# 230721-.net
KiCad netlist of a schematic drawn in EasyEDA Pro
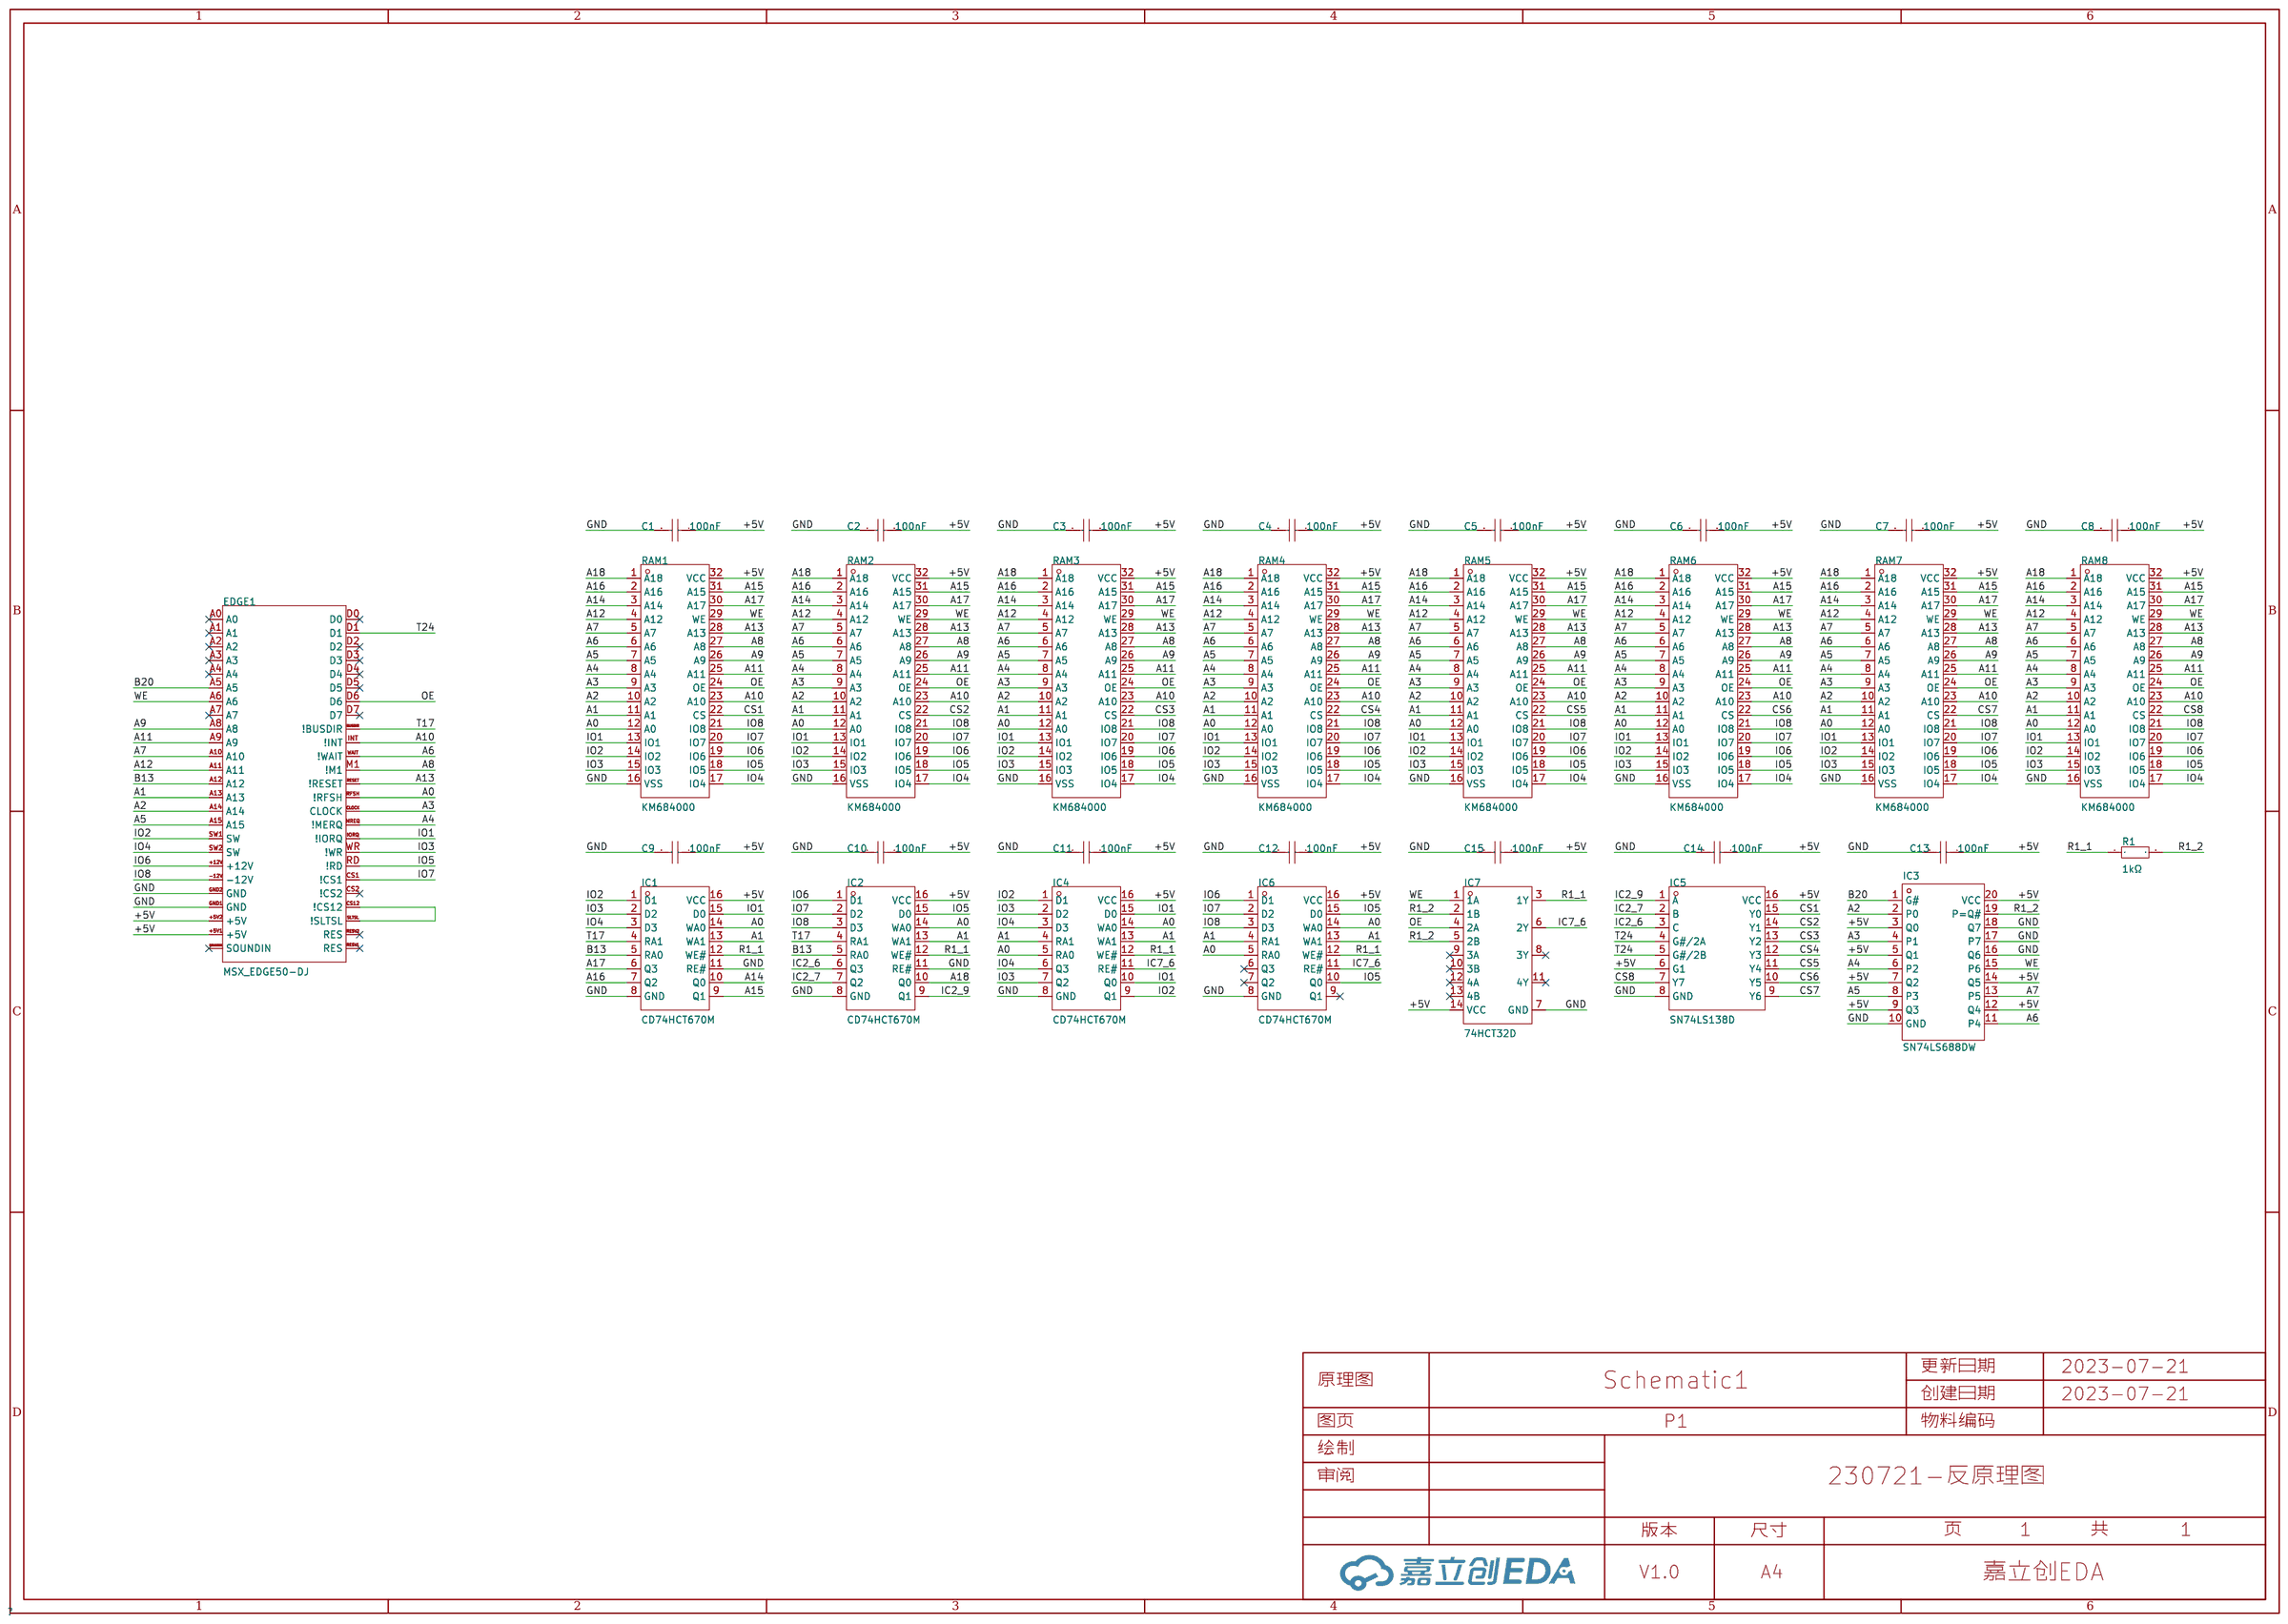
[diagram p0: schematic sheet]

(export (version "E")
  (design (tool "Eeschema 10.0.6"))
  (components
    (comp (ref "C1")
      (value "100nF")
      (footprint "easyedapro:C0805")
      (description "容值:100nF;精度:±10%;额定电压:50V;材质(温度系数):X7R;")
      (fields
        (field (name "Manufacturer Part") "CC0805KRX7R9BB104")
        (field (name "Manufacturer") "YAGEO(国巨)")
      )
      (libsource (lib "easyedapro") (part "CC0805KRX7R9BB104"))
    )
    (comp (ref "C2")
      (value "100nF")
      (footprint "easyedapro:C0805")
      (description "容值:100nF;精度:±10%;额定电压:50V;材质(温度系数):X7R;")
      (fields
        (field (name "Manufacturer Part") "CC0805KRX7R9BB104")
        (field (name "Manufacturer") "YAGEO(国巨)")
      )
      (libsource (lib "easyedapro") (part "CC0805KRX7R9BB104"))
    )
    (comp (ref "C3")
      (value "100nF")
      (footprint "easyedapro:C0805")
      (description "容值:100nF;精度:±10%;额定电压:50V;材质(温度系数):X7R;")
      (fields
        (field (name "Manufacturer Part") "CC0805KRX7R9BB104")
        (field (name "Manufacturer") "YAGEO(国巨)")
      )
      (libsource (lib "easyedapro") (part "CC0805KRX7R9BB104"))
    )
    (comp (ref "C4")
      (value "100nF")
      (footprint "easyedapro:C0805")
      (description "容值:100nF;精度:±10%;额定电压:50V;材质(温度系数):X7R;")
      (fields
        (field (name "Manufacturer Part") "CC0805KRX7R9BB104")
        (field (name "Manufacturer") "YAGEO(国巨)")
      )
      (libsource (lib "easyedapro") (part "CC0805KRX7R9BB104"))
    )
    (comp (ref "C5")
      (value "100nF")
      (footprint "easyedapro:C0805")
      (description "容值:100nF;精度:±10%;额定电压:50V;材质(温度系数):X7R;")
      (fields
        (field (name "Manufacturer Part") "CC0805KRX7R9BB104")
        (field (name "Manufacturer") "YAGEO(国巨)")
      )
      (libsource (lib "easyedapro") (part "CC0805KRX7R9BB104"))
    )
    (comp (ref "C6")
      (value "100nF")
      (footprint "easyedapro:C0805")
      (description "容值:100nF;精度:±10%;额定电压:50V;材质(温度系数):X7R;")
      (fields
        (field (name "Manufacturer Part") "CC0805KRX7R9BB104")
        (field (name "Manufacturer") "YAGEO(国巨)")
      )
      (libsource (lib "easyedapro") (part "CC0805KRX7R9BB104"))
    )
    (comp (ref "C7")
      (value "100nF")
      (footprint "easyedapro:C0805")
      (description "容值:100nF;精度:±10%;额定电压:50V;材质(温度系数):X7R;")
      (fields
        (field (name "Manufacturer Part") "CC0805KRX7R9BB104")
        (field (name "Manufacturer") "YAGEO(国巨)")
      )
      (libsource (lib "easyedapro") (part "CC0805KRX7R9BB104"))
    )
    (comp (ref "C8")
      (value "100nF")
      (footprint "easyedapro:C0805")
      (description "容值:100nF;精度:±10%;额定电压:50V;材质(温度系数):X7R;")
      (fields
        (field (name "Manufacturer Part") "CC0805KRX7R9BB104")
        (field (name "Manufacturer") "YAGEO(国巨)")
      )
      (libsource (lib "easyedapro") (part "CC0805KRX7R9BB104"))
    )
    (comp (ref "C9")
      (value "100nF")
      (footprint "easyedapro:C0805")
      (description "容值:100nF;精度:±10%;额定电压:50V;材质(温度系数):X7R;")
      (fields
        (field (name "Manufacturer Part") "CC0805KRX7R9BB104")
        (field (name "Manufacturer") "YAGEO(国巨)")
      )
      (libsource (lib "easyedapro") (part "CC0805KRX7R9BB104"))
    )
    (comp (ref "C10")
      (value "100nF")
      (footprint "easyedapro:C0805")
      (description "容值:100nF;精度:±10%;额定电压:50V;材质(温度系数):X7R;")
      (fields
        (field (name "Manufacturer Part") "CC0805KRX7R9BB104")
        (field (name "Manufacturer") "YAGEO(国巨)")
      )
      (libsource (lib "easyedapro") (part "CC0805KRX7R9BB104"))
    )
    (comp (ref "C11")
      (value "100nF")
      (footprint "easyedapro:C0805")
      (description "容值:100nF;精度:±10%;额定电压:50V;材质(温度系数):X7R;")
      (fields
        (field (name "Manufacturer Part") "CC0805KRX7R9BB104")
        (field (name "Manufacturer") "YAGEO(国巨)")
      )
      (libsource (lib "easyedapro") (part "CC0805KRX7R9BB104"))
    )
    (comp (ref "C12")
      (value "100nF")
      (footprint "easyedapro:C0805")
      (description "容值:100nF;精度:±10%;额定电压:50V;材质(温度系数):X7R;")
      (fields
        (field (name "Manufacturer Part") "CC0805KRX7R9BB104")
        (field (name "Manufacturer") "YAGEO(国巨)")
      )
      (libsource (lib "easyedapro") (part "CC0805KRX7R9BB104"))
    )
    (comp (ref "C13")
      (value "100nF")
      (footprint "easyedapro:C0805")
      (description "容值:100nF;精度:±10%;额定电压:50V;材质(温度系数):X7R;")
      (fields
        (field (name "Manufacturer Part") "CC0805KRX7R9BB104")
        (field (name "Manufacturer") "YAGEO(国巨)")
      )
      (libsource (lib "easyedapro") (part "CC0805KRX7R9BB104"))
    )
    (comp (ref "C14")
      (value "100nF")
      (footprint "easyedapro:C0805")
      (description "容值:100nF;精度:±10%;额定电压:50V;材质(温度系数):X7R;")
      (fields
        (field (name "Manufacturer Part") "CC0805KRX7R9BB104")
        (field (name "Manufacturer") "YAGEO(国巨)")
      )
      (libsource (lib "easyedapro") (part "CC0805KRX7R9BB104"))
    )
    (comp (ref "C15")
      (value "100nF")
      (footprint "easyedapro:C0805")
      (description "容值:100nF;精度:±10%;额定电压:50V;材质(温度系数):X7R;")
      (fields
        (field (name "Manufacturer Part") "CC0805KRX7R9BB104")
        (field (name "Manufacturer") "YAGEO(国巨)")
      )
      (libsource (lib "easyedapro") (part "CC0805KRX7R9BB104"))
    )
    (comp (ref "EDGE1")
      (value "MSX_EDGE50-DJ")
      (footprint "easyedapro:MSXCART_DJ")
      (libsource (lib "easyedapro") (part "MSX_EDGE50-DJ"))
    )
    (comp (ref "IC1")
      (value "CD74HCT670M")
      (footprint "easyedapro:SOIC-16_L9.9-W3.9-P1.27-LS6.0-BL")
      (description "高速 CMOS 逻辑 4 x 4 寄存器文件 16-SOIC -55 to 125")
      (fields (field (name "Manufacturer") "TI(德州仪器)"))
      (libsource (lib "easyedapro") (part "CD74HCT670M"))
    )
    (comp (ref "IC2")
      (value "CD74HCT670M")
      (footprint "easyedapro:SOIC-16_L9.9-W3.9-P1.27-LS6.0-BL")
      (description "高速 CMOS 逻辑 4 x 4 寄存器文件 16-SOIC -55 to 125")
      (fields (field (name "Manufacturer") "TI(德州仪器)"))
      (libsource (lib "easyedapro") (part "CD74HCT670M"))
    )
    (comp (ref "IC3")
      (value "SN74LS688DW")
      (footprint "easyedapro:SOIC-20_L12.8-W7.5-P1.27-LS10.3-BL")
      (description "具有使能端的 8 位等值/幅度比较器 (P=Q) 20-SOIC 0 to 70")
      (fields (field (name "Manufacturer") "TI(德州仪器)"))
      (libsource (lib "easyedapro") (part "SN74LS688DW"))
    )
    (comp (ref "IC4")
      (value "CD74HCT670M")
      (footprint "easyedapro:SOIC-16_L9.9-W3.9-P1.27-LS6.0-BL")
      (description "高速 CMOS 逻辑 4 x 4 寄存器文件 16-SOIC -55 to 125")
      (fields (field (name "Manufacturer") "TI(德州仪器)"))
      (libsource (lib "easyedapro") (part "CD74HCT670M"))
    )
    (comp (ref "IC5")
      (value "SN74LS138D")
      (footprint "easyedapro:SOIC-16_L9.9-W3.9-P1.27-LS6.0-BL")
      (description "类型:解码器/多路解器;低电平输出电流(IOL):8mA;高电平输出电流(IOH):400uA;供电电源:单电源;供电电压:4.75V~5.25V;工作温度:0°C~+70°C;")
      (fields (field (name "Manufacturer") "TI(德州仪器)"))
      (libsource (lib "easyedapro") (part "SN74LS138D"))
    )
    (comp (ref "IC6")
      (value "CD74HCT670M")
      (footprint "easyedapro:SOIC-16_L9.9-W3.9-P1.27-LS6.0-BL")
      (description "高速 CMOS 逻辑 4 x 4 寄存器文件 16-SOIC -55 to 125")
      (fields (field (name "Manufacturer") "TI(德州仪器)"))
      (libsource (lib "easyedapro") (part "CD74HCT670M"))
    )
    (comp (ref "IC7")
      (value "74HCT32D")
      (footprint "easyedapro:SOIC-14_L8.6-W3.9-P1.27-LS6.0-BL")
      (description "逻辑类型:或门;通道数:4;电源电压:4.5V~5.5V;静态电流(最大值):1uA;最大传播延迟:18ns@5.5V,50pF;")
      (fields (field (name "Manufacturer") "TOSHIBA(东芝)"))
      (libsource (lib "easyedapro") (part "74HCT32D"))
    )
    (comp (ref "R1")
      (value "1kΩ")
      (footprint "easyedapro:R0805")
      (description "电阻类型:厚膜电阻;阻值:1kΩ;精度:±1%;功率:125mW;")
      (fields
        (field (name "Manufacturer Part") "0805W8F1001T5E")
        (field (name "Manufacturer") "UNI-ROYAL(厚声)")
      )
      (libsource (lib "easyedapro") (part "0805W8F1001T5E"))
    )
    (comp (ref "RAM1")
      (value "KM684000")
      (footprint "easyedapro:SOP-32_L20.9-W11.4-P1.27-LS14.12-BL")
      (description "存储器类型:-;存储器容量:-;存储器接口类型:-;工作电压:-;")
      (libsource (lib "easyedapro") (part "KM684000"))
    )
    (comp (ref "RAM2")
      (value "KM684000")
      (footprint "easyedapro:SOP-32_L20.9-W11.4-P1.27-LS14.12-BL")
      (description "存储器类型:-;存储器容量:-;存储器接口类型:-;工作电压:-;")
      (libsource (lib "easyedapro") (part "KM684000"))
    )
    (comp (ref "RAM3")
      (value "KM684000")
      (footprint "easyedapro:SOP-32_L20.9-W11.4-P1.27-LS14.12-BL")
      (description "存储器类型:-;存储器容量:-;存储器接口类型:-;工作电压:-;")
      (libsource (lib "easyedapro") (part "KM684000"))
    )
    (comp (ref "RAM4")
      (value "KM684000")
      (footprint "easyedapro:SOP-32_L20.9-W11.4-P1.27-LS14.12-BL")
      (description "存储器类型:-;存储器容量:-;存储器接口类型:-;工作电压:-;")
      (libsource (lib "easyedapro") (part "KM684000"))
    )
    (comp (ref "RAM5")
      (value "KM684000")
      (footprint "easyedapro:SOP-32_L20.9-W11.4-P1.27-LS14.12-BL")
      (description "存储器类型:-;存储器容量:-;存储器接口类型:-;工作电压:-;")
      (libsource (lib "easyedapro") (part "KM684000"))
    )
    (comp (ref "RAM6")
      (value "KM684000")
      (footprint "easyedapro:SOP-32_L20.9-W11.4-P1.27-LS14.12-BL")
      (description "存储器类型:-;存储器容量:-;存储器接口类型:-;工作电压:-;")
      (libsource (lib "easyedapro") (part "KM684000"))
    )
    (comp (ref "RAM7")
      (value "KM684000")
      (footprint "easyedapro:SOP-32_L20.9-W11.4-P1.27-LS14.12-BL")
      (description "存储器类型:-;存储器容量:-;存储器接口类型:-;工作电压:-;")
      (libsource (lib "easyedapro") (part "KM684000"))
    )
    (comp (ref "RAM8")
      (value "KM684000")
      (footprint "easyedapro:SOP-32_L20.9-W11.4-P1.27-LS14.12-BL")
      (description "存储器类型:-;存储器容量:-;存储器接口类型:-;工作电压:-;")
      (libsource (lib "easyedapro") (part "KM684000"))
    )
  )
  (nets
    (net (code "1") (name "/+5V") (class "Default")
      (node (ref "C1") (pin "1") (pinfunction "1_1") (pintype "input"))
      (node (ref "C10") (pin "1") (pinfunction "1_1") (pintype "input"))
      (node (ref "C11") (pin "1") (pinfunction "1_1") (pintype "input"))
      (node (ref "C12") (pin "1") (pinfunction "1_1") (pintype "input"))
      (node (ref "C13") (pin "1") (pinfunction "1_1") (pintype "input"))
      (node (ref "C14") (pin "1") (pinfunction "1_1") (pintype "input"))
      (node (ref "C15") (pin "1") (pinfunction "1_1") (pintype "input"))
      (node (ref "C2") (pin "1") (pinfunction "1_1") (pintype "input"))
      (node (ref "C3") (pin "1") (pinfunction "1_1") (pintype "input"))
      (node (ref "C4") (pin "1") (pinfunction "1_1") (pintype "input"))
      (node (ref "C5") (pin "1") (pinfunction "1_1") (pintype "input"))
      (node (ref "C6") (pin "1") (pinfunction "1_1") (pintype "input"))
      (node (ref "C7") (pin "1") (pinfunction "1_1") (pintype "input"))
      (node (ref "C8") (pin "1") (pinfunction "1_1") (pintype "input"))
      (node (ref "C9") (pin "1") (pinfunction "1_1") (pintype "input"))
      (node (ref "EDGE1") (pin "+5V1") (pinfunction "+5V_+5V1") (pintype "input"))
      (node (ref "EDGE1") (pin "+5V2") (pinfunction "+5V_+5V2") (pintype "input"))
      (node (ref "IC1") (pin "16") (pinfunction "VCC_16") (pintype "input"))
      (node (ref "IC2") (pin "16") (pinfunction "VCC_16") (pintype "input"))
      (node (ref "IC3") (pin "12") (pinfunction "Q4_12") (pintype "input"))
      (node (ref "IC3") (pin "14") (pinfunction "Q5_14") (pintype "input"))
      (node (ref "IC3") (pin "20") (pinfunction "VCC_20") (pintype "input"))
      (node (ref "IC3") (pin "3") (pinfunction "Q0_3") (pintype "input"))
      (node (ref "IC3") (pin "5") (pinfunction "Q1_5") (pintype "input"))
      (node (ref "IC3") (pin "7") (pinfunction "Q2_7") (pintype "input"))
      (node (ref "IC3") (pin "9") (pinfunction "Q3_9") (pintype "input"))
      (node (ref "IC4") (pin "16") (pinfunction "VCC_16") (pintype "input"))
      (node (ref "IC5") (pin "16") (pinfunction "VCC_16") (pintype "input"))
      (node (ref "IC5") (pin "6") (pinfunction "G1_6") (pintype "input"))
      (node (ref "IC6") (pin "16") (pinfunction "VCC_16") (pintype "input"))
      (node (ref "IC7") (pin "14") (pinfunction "VCC_14") (pintype "input"))
      (node (ref "RAM1") (pin "32") (pinfunction "VCC_32") (pintype "input"))
      (node (ref "RAM2") (pin "32") (pinfunction "VCC_32") (pintype "input"))
      (node (ref "RAM3") (pin "32") (pinfunction "VCC_32") (pintype "input"))
      (node (ref "RAM4") (pin "32") (pinfunction "VCC_32") (pintype "input"))
      (node (ref "RAM5") (pin "32") (pinfunction "VCC_32") (pintype "input"))
      (node (ref "RAM6") (pin "32") (pinfunction "VCC_32") (pintype "input"))
      (node (ref "RAM7") (pin "32") (pinfunction "VCC_32") (pintype "input"))
      (node (ref "RAM8") (pin "32") (pinfunction "VCC_32") (pintype "input"))
    )
    (net (code "2") (name "/A0") (class "Default")
      (node (ref "EDGE1") (pin "RFSH") (pinfunction "!RFSH_RFSH") (pintype "output"))
      (node (ref "IC1") (pin "14") (pinfunction "WA0_14") (pintype "input"))
      (node (ref "IC2") (pin "14") (pinfunction "WA0_14") (pintype "input"))
      (node (ref "IC4") (pin "14") (pinfunction "WA0_14") (pintype "input"))
      (node (ref "IC4") (pin "5") (pinfunction "RA0_5") (pintype "input"))
      (node (ref "IC6") (pin "14") (pinfunction "WA0_14") (pintype "input"))
      (node (ref "IC6") (pin "5") (pinfunction "RA0_5") (pintype "input"))
      (node (ref "RAM1") (pin "12") (pinfunction "A0_12") (pintype "input"))
      (node (ref "RAM2") (pin "12") (pinfunction "A0_12") (pintype "input"))
      (node (ref "RAM3") (pin "12") (pinfunction "A0_12") (pintype "input"))
      (node (ref "RAM4") (pin "12") (pinfunction "A0_12") (pintype "input"))
      (node (ref "RAM5") (pin "12") (pinfunction "A0_12") (pintype "input"))
      (node (ref "RAM6") (pin "12") (pinfunction "A0_12") (pintype "input"))
      (node (ref "RAM7") (pin "12") (pinfunction "A0_12") (pintype "input"))
      (node (ref "RAM8") (pin "12") (pinfunction "A0_12") (pintype "input"))
    )
    (net (code "3") (name "/A1") (class "Default")
      (node (ref "EDGE1") (pin "A13") (pinfunction "A13_A13") (pintype "output"))
      (node (ref "IC1") (pin "13") (pinfunction "WA1_13") (pintype "input"))
      (node (ref "IC2") (pin "13") (pinfunction "WA1_13") (pintype "input"))
      (node (ref "IC4") (pin "13") (pinfunction "WA1_13") (pintype "input"))
      (node (ref "IC4") (pin "4") (pinfunction "RA1_4") (pintype "input"))
      (node (ref "IC6") (pin "13") (pinfunction "WA1_13") (pintype "input"))
      (node (ref "IC6") (pin "4") (pinfunction "RA1_4") (pintype "input"))
      (node (ref "RAM1") (pin "11") (pinfunction "A1_11") (pintype "input"))
      (node (ref "RAM2") (pin "11") (pinfunction "A1_11") (pintype "input"))
      (node (ref "RAM3") (pin "11") (pinfunction "A1_11") (pintype "input"))
      (node (ref "RAM4") (pin "11") (pinfunction "A1_11") (pintype "input"))
      (node (ref "RAM5") (pin "11") (pinfunction "A1_11") (pintype "input"))
      (node (ref "RAM6") (pin "11") (pinfunction "A1_11") (pintype "input"))
      (node (ref "RAM7") (pin "11") (pinfunction "A1_11") (pintype "input"))
      (node (ref "RAM8") (pin "11") (pinfunction "A1_11") (pintype "input"))
    )
    (net (code "4") (name "/A2") (class "Default")
      (node (ref "EDGE1") (pin "A14") (pinfunction "A14_A14") (pintype "output"))
      (node (ref "IC3") (pin "2") (pinfunction "P0_2") (pintype "input"))
      (node (ref "RAM1") (pin "10") (pinfunction "A2_10") (pintype "input"))
      (node (ref "RAM2") (pin "10") (pinfunction "A2_10") (pintype "input"))
      (node (ref "RAM3") (pin "10") (pinfunction "A2_10") (pintype "input"))
      (node (ref "RAM4") (pin "10") (pinfunction "A2_10") (pintype "input"))
      (node (ref "RAM5") (pin "10") (pinfunction "A2_10") (pintype "input"))
      (node (ref "RAM6") (pin "10") (pinfunction "A2_10") (pintype "input"))
      (node (ref "RAM7") (pin "10") (pinfunction "A2_10") (pintype "input"))
      (node (ref "RAM8") (pin "10") (pinfunction "A2_10") (pintype "input"))
    )
    (net (code "5") (name "/A3") (class "Default")
      (node (ref "EDGE1") (pin "CLOCK") (pinfunction "CLOCK_CLOCK") (pintype "output"))
      (node (ref "IC3") (pin "4") (pinfunction "P1_4") (pintype "input"))
      (node (ref "RAM1") (pin "9") (pinfunction "A3_9") (pintype "input"))
      (node (ref "RAM2") (pin "9") (pinfunction "A3_9") (pintype "input"))
      (node (ref "RAM3") (pin "9") (pinfunction "A3_9") (pintype "input"))
      (node (ref "RAM4") (pin "9") (pinfunction "A3_9") (pintype "input"))
      (node (ref "RAM5") (pin "9") (pinfunction "A3_9") (pintype "input"))
      (node (ref "RAM6") (pin "9") (pinfunction "A3_9") (pintype "input"))
      (node (ref "RAM7") (pin "9") (pinfunction "A3_9") (pintype "input"))
      (node (ref "RAM8") (pin "9") (pinfunction "A3_9") (pintype "input"))
    )
    (net (code "6") (name "/A4") (class "Default")
      (node (ref "EDGE1") (pin "MREQ") (pinfunction "!MERQ_MREQ") (pintype "output"))
      (node (ref "IC3") (pin "6") (pinfunction "P2_6") (pintype "input"))
      (node (ref "RAM1") (pin "8") (pinfunction "A4_8") (pintype "input"))
      (node (ref "RAM2") (pin "8") (pinfunction "A4_8") (pintype "input"))
      (node (ref "RAM3") (pin "8") (pinfunction "A4_8") (pintype "input"))
      (node (ref "RAM4") (pin "8") (pinfunction "A4_8") (pintype "input"))
      (node (ref "RAM5") (pin "8") (pinfunction "A4_8") (pintype "input"))
      (node (ref "RAM6") (pin "8") (pinfunction "A4_8") (pintype "input"))
      (node (ref "RAM7") (pin "8") (pinfunction "A4_8") (pintype "input"))
      (node (ref "RAM8") (pin "8") (pinfunction "A4_8") (pintype "input"))
    )
    (net (code "7") (name "/A5") (class "Default")
      (node (ref "EDGE1") (pin "A15") (pinfunction "A15_A15") (pintype "output"))
      (node (ref "IC3") (pin "8") (pinfunction "P3_8") (pintype "input"))
      (node (ref "RAM1") (pin "7") (pinfunction "A5_7") (pintype "input"))
      (node (ref "RAM2") (pin "7") (pinfunction "A5_7") (pintype "input"))
      (node (ref "RAM3") (pin "7") (pinfunction "A5_7") (pintype "input"))
      (node (ref "RAM4") (pin "7") (pinfunction "A5_7") (pintype "input"))
      (node (ref "RAM5") (pin "7") (pinfunction "A5_7") (pintype "input"))
      (node (ref "RAM6") (pin "7") (pinfunction "A5_7") (pintype "input"))
      (node (ref "RAM7") (pin "7") (pinfunction "A5_7") (pintype "input"))
      (node (ref "RAM8") (pin "7") (pinfunction "A5_7") (pintype "input"))
    )
    (net (code "8") (name "/A6") (class "Default")
      (node (ref "EDGE1") (pin "WAIT") (pinfunction "!WAIT_WAIT") (pintype "input"))
      (node (ref "IC3") (pin "11") (pinfunction "P4_11") (pintype "input"))
      (node (ref "RAM1") (pin "6") (pinfunction "A6_6") (pintype "input"))
      (node (ref "RAM2") (pin "6") (pinfunction "A6_6") (pintype "input"))
      (node (ref "RAM3") (pin "6") (pinfunction "A6_6") (pintype "input"))
      (node (ref "RAM4") (pin "6") (pinfunction "A6_6") (pintype "input"))
      (node (ref "RAM5") (pin "6") (pinfunction "A6_6") (pintype "input"))
      (node (ref "RAM6") (pin "6") (pinfunction "A6_6") (pintype "input"))
      (node (ref "RAM7") (pin "6") (pinfunction "A6_6") (pintype "input"))
      (node (ref "RAM8") (pin "6") (pinfunction "A6_6") (pintype "input"))
    )
    (net (code "9") (name "/A7") (class "Default")
      (node (ref "EDGE1") (pin "A10") (pinfunction "A10_A10") (pintype "output"))
      (node (ref "IC3") (pin "13") (pinfunction "P5_13") (pintype "input"))
      (node (ref "RAM1") (pin "5") (pinfunction "A7_5") (pintype "input"))
      (node (ref "RAM2") (pin "5") (pinfunction "A7_5") (pintype "input"))
      (node (ref "RAM3") (pin "5") (pinfunction "A7_5") (pintype "input"))
      (node (ref "RAM4") (pin "5") (pinfunction "A7_5") (pintype "input"))
      (node (ref "RAM5") (pin "5") (pinfunction "A7_5") (pintype "input"))
      (node (ref "RAM6") (pin "5") (pinfunction "A7_5") (pintype "input"))
      (node (ref "RAM7") (pin "5") (pinfunction "A7_5") (pintype "input"))
      (node (ref "RAM8") (pin "5") (pinfunction "A7_5") (pintype "input"))
    )
    (net (code "10") (name "/A8") (class "Default")
      (node (ref "EDGE1") (pin "M1") (pinfunction "!M1_M1") (pintype "output"))
      (node (ref "RAM1") (pin "27") (pinfunction "A8_27") (pintype "input"))
      (node (ref "RAM2") (pin "27") (pinfunction "A8_27") (pintype "input"))
      (node (ref "RAM3") (pin "27") (pinfunction "A8_27") (pintype "input"))
      (node (ref "RAM4") (pin "27") (pinfunction "A8_27") (pintype "input"))
      (node (ref "RAM5") (pin "27") (pinfunction "A8_27") (pintype "input"))
      (node (ref "RAM6") (pin "27") (pinfunction "A8_27") (pintype "input"))
      (node (ref "RAM7") (pin "27") (pinfunction "A8_27") (pintype "input"))
      (node (ref "RAM8") (pin "27") (pinfunction "A8_27") (pintype "input"))
    )
    (net (code "11") (name "/A9") (class "Default")
      (node (ref "EDGE1") (pin "A8") (pinfunction "A8_A8") (pintype "output"))
      (node (ref "RAM1") (pin "26") (pinfunction "A9_26") (pintype "input"))
      (node (ref "RAM2") (pin "26") (pinfunction "A9_26") (pintype "input"))
      (node (ref "RAM3") (pin "26") (pinfunction "A9_26") (pintype "input"))
      (node (ref "RAM4") (pin "26") (pinfunction "A9_26") (pintype "input"))
      (node (ref "RAM5") (pin "26") (pinfunction "A9_26") (pintype "input"))
      (node (ref "RAM6") (pin "26") (pinfunction "A9_26") (pintype "input"))
      (node (ref "RAM7") (pin "26") (pinfunction "A9_26") (pintype "input"))
      (node (ref "RAM8") (pin "26") (pinfunction "A9_26") (pintype "input"))
    )
    (net (code "12") (name "/A10") (class "Default")
      (node (ref "EDGE1") (pin "INT") (pinfunction "!INT_INT") (pintype "input"))
      (node (ref "RAM1") (pin "23") (pinfunction "A10_23") (pintype "input"))
      (node (ref "RAM2") (pin "23") (pinfunction "A10_23") (pintype "input"))
      (node (ref "RAM3") (pin "23") (pinfunction "A10_23") (pintype "input"))
      (node (ref "RAM4") (pin "23") (pinfunction "A10_23") (pintype "input"))
      (node (ref "RAM5") (pin "23") (pinfunction "A10_23") (pintype "input"))
      (node (ref "RAM6") (pin "23") (pinfunction "A10_23") (pintype "input"))
      (node (ref "RAM7") (pin "23") (pinfunction "A10_23") (pintype "input"))
      (node (ref "RAM8") (pin "23") (pinfunction "A10_23") (pintype "input"))
    )
    (net (code "13") (name "/A11") (class "Default")
      (node (ref "EDGE1") (pin "A9") (pinfunction "A9_A9") (pintype "output"))
      (node (ref "RAM1") (pin "25") (pinfunction "A11_25") (pintype "input"))
      (node (ref "RAM2") (pin "25") (pinfunction "A11_25") (pintype "input"))
      (node (ref "RAM3") (pin "25") (pinfunction "A11_25") (pintype "input"))
      (node (ref "RAM4") (pin "25") (pinfunction "A11_25") (pintype "input"))
      (node (ref "RAM5") (pin "25") (pinfunction "A11_25") (pintype "input"))
      (node (ref "RAM6") (pin "25") (pinfunction "A11_25") (pintype "input"))
      (node (ref "RAM7") (pin "25") (pinfunction "A11_25") (pintype "input"))
      (node (ref "RAM8") (pin "25") (pinfunction "A11_25") (pintype "input"))
    )
    (net (code "14") (name "/A12") (class "Default")
      (node (ref "EDGE1") (pin "A11") (pinfunction "A11_A11") (pintype "output"))
      (node (ref "RAM1") (pin "4") (pinfunction "A12_4") (pintype "input"))
      (node (ref "RAM2") (pin "4") (pinfunction "A12_4") (pintype "input"))
      (node (ref "RAM3") (pin "4") (pinfunction "A12_4") (pintype "input"))
      (node (ref "RAM4") (pin "4") (pinfunction "A12_4") (pintype "input"))
      (node (ref "RAM5") (pin "4") (pinfunction "A12_4") (pintype "input"))
      (node (ref "RAM6") (pin "4") (pinfunction "A12_4") (pintype "input"))
      (node (ref "RAM7") (pin "4") (pinfunction "A12_4") (pintype "input"))
      (node (ref "RAM8") (pin "4") (pinfunction "A12_4") (pintype "input"))
    )
    (net (code "15") (name "/A13") (class "Default")
      (node (ref "EDGE1") (pin "RESET") (pinfunction "!RESET_RESET") (pintype "output"))
      (node (ref "RAM1") (pin "28") (pinfunction "A13_28") (pintype "input"))
      (node (ref "RAM2") (pin "28") (pinfunction "A13_28") (pintype "input"))
      (node (ref "RAM3") (pin "28") (pinfunction "A13_28") (pintype "input"))
      (node (ref "RAM4") (pin "28") (pinfunction "A13_28") (pintype "input"))
      (node (ref "RAM5") (pin "28") (pinfunction "A13_28") (pintype "input"))
      (node (ref "RAM6") (pin "28") (pinfunction "A13_28") (pintype "input"))
      (node (ref "RAM7") (pin "28") (pinfunction "A13_28") (pintype "input"))
      (node (ref "RAM8") (pin "28") (pinfunction "A13_28") (pintype "input"))
    )
    (net (code "16") (name "/A14") (class "Default")
      (node (ref "IC1") (pin "10") (pinfunction "Q0_10") (pintype "input"))
      (node (ref "RAM1") (pin "3") (pinfunction "A14_3") (pintype "input"))
      (node (ref "RAM2") (pin "3") (pinfunction "A14_3") (pintype "input"))
      (node (ref "RAM3") (pin "3") (pinfunction "A14_3") (pintype "input"))
      (node (ref "RAM4") (pin "3") (pinfunction "A14_3") (pintype "input"))
      (node (ref "RAM5") (pin "3") (pinfunction "A14_3") (pintype "input"))
      (node (ref "RAM6") (pin "3") (pinfunction "A14_3") (pintype "input"))
      (node (ref "RAM7") (pin "3") (pinfunction "A14_3") (pintype "input"))
      (node (ref "RAM8") (pin "3") (pinfunction "A14_3") (pintype "input"))
    )
    (net (code "17") (name "/A15") (class "Default")
      (node (ref "IC1") (pin "9") (pinfunction "Q1_9") (pintype "input"))
      (node (ref "RAM1") (pin "31") (pinfunction "A15_31") (pintype "input"))
      (node (ref "RAM2") (pin "31") (pinfunction "A15_31") (pintype "input"))
      (node (ref "RAM3") (pin "31") (pinfunction "A15_31") (pintype "input"))
      (node (ref "RAM4") (pin "31") (pinfunction "A15_31") (pintype "input"))
      (node (ref "RAM5") (pin "31") (pinfunction "A15_31") (pintype "input"))
      (node (ref "RAM6") (pin "31") (pinfunction "A15_31") (pintype "input"))
      (node (ref "RAM7") (pin "31") (pinfunction "A15_31") (pintype "input"))
      (node (ref "RAM8") (pin "31") (pinfunction "A15_31") (pintype "input"))
    )
    (net (code "18") (name "/A16") (class "Default")
      (node (ref "IC1") (pin "7") (pinfunction "Q2_7") (pintype "input"))
      (node (ref "RAM1") (pin "2") (pinfunction "A16_2") (pintype "input"))
      (node (ref "RAM2") (pin "2") (pinfunction "A16_2") (pintype "input"))
      (node (ref "RAM3") (pin "2") (pinfunction "A16_2") (pintype "input"))
      (node (ref "RAM4") (pin "2") (pinfunction "A16_2") (pintype "input"))
      (node (ref "RAM5") (pin "2") (pinfunction "A16_2") (pintype "input"))
      (node (ref "RAM6") (pin "2") (pinfunction "A16_2") (pintype "input"))
      (node (ref "RAM7") (pin "2") (pinfunction "A16_2") (pintype "input"))
      (node (ref "RAM8") (pin "2") (pinfunction "A16_2") (pintype "input"))
    )
    (net (code "19") (name "/A17") (class "Default")
      (node (ref "IC1") (pin "6") (pinfunction "Q3_6") (pintype "input"))
      (node (ref "RAM1") (pin "30") (pinfunction "A17_30") (pintype "input"))
      (node (ref "RAM2") (pin "30") (pinfunction "A17_30") (pintype "input"))
      (node (ref "RAM3") (pin "30") (pinfunction "A17_30") (pintype "input"))
      (node (ref "RAM4") (pin "30") (pinfunction "A17_30") (pintype "input"))
      (node (ref "RAM5") (pin "30") (pinfunction "A17_30") (pintype "input"))
      (node (ref "RAM6") (pin "30") (pinfunction "A17_30") (pintype "input"))
      (node (ref "RAM7") (pin "30") (pinfunction "A17_30") (pintype "input"))
      (node (ref "RAM8") (pin "30") (pinfunction "A17_30") (pintype "input"))
    )
    (net (code "20") (name "/A18") (class "Default")
      (node (ref "IC2") (pin "10") (pinfunction "Q0_10") (pintype "input"))
      (node (ref "RAM1") (pin "1") (pinfunction "A18_1") (pintype "input"))
      (node (ref "RAM2") (pin "1") (pinfunction "A18_1") (pintype "input"))
      (node (ref "RAM3") (pin "1") (pinfunction "A18_1") (pintype "input"))
      (node (ref "RAM4") (pin "1") (pinfunction "A18_1") (pintype "input"))
      (node (ref "RAM5") (pin "1") (pinfunction "A18_1") (pintype "input"))
      (node (ref "RAM6") (pin "1") (pinfunction "A18_1") (pintype "input"))
      (node (ref "RAM7") (pin "1") (pinfunction "A18_1") (pintype "input"))
      (node (ref "RAM8") (pin "1") (pinfunction "A18_1") (pintype "input"))
    )
    (net (code "21") (name "/B13") (class "Default")
      (node (ref "EDGE1") (pin "A12") (pinfunction "A12_A12") (pintype "output"))
      (node (ref "IC1") (pin "5") (pinfunction "RA0_5") (pintype "input"))
      (node (ref "IC2") (pin "5") (pinfunction "RA0_5") (pintype "input"))
    )
    (net (code "22") (name "/B20") (class "Default")
      (node (ref "EDGE1") (pin "A5") (pinfunction "A5_A5") (pintype "output"))
      (node (ref "IC3") (pin "1") (pinfunction "G#_1") (pintype "input"))
    )
    (net (code "23") (name "/CS1") (class "Default")
      (node (ref "IC5") (pin "15") (pinfunction "Y0_15") (pintype "input"))
      (node (ref "RAM1") (pin "22") (pinfunction "CS_22") (pintype "input"))
    )
    (net (code "24") (name "/CS2") (class "Default")
      (node (ref "IC5") (pin "14") (pinfunction "Y1_14") (pintype "input"))
      (node (ref "RAM2") (pin "22") (pinfunction "CS_22") (pintype "input"))
    )
    (net (code "25") (name "/CS3") (class "Default")
      (node (ref "IC5") (pin "13") (pinfunction "Y2_13") (pintype "input"))
      (node (ref "RAM3") (pin "22") (pinfunction "CS_22") (pintype "input"))
    )
    (net (code "26") (name "/CS4") (class "Default")
      (node (ref "IC5") (pin "12") (pinfunction "Y3_12") (pintype "input"))
      (node (ref "RAM4") (pin "22") (pinfunction "CS_22") (pintype "input"))
    )
    (net (code "27") (name "/CS5") (class "Default")
      (node (ref "IC5") (pin "11") (pinfunction "Y4_11") (pintype "input"))
      (node (ref "RAM5") (pin "22") (pinfunction "CS_22") (pintype "input"))
    )
    (net (code "28") (name "/CS6") (class "Default")
      (node (ref "IC5") (pin "10") (pinfunction "Y5_10") (pintype "input"))
      (node (ref "RAM6") (pin "22") (pinfunction "CS_22") (pintype "input"))
    )
    (net (code "29") (name "/CS7") (class "Default")
      (node (ref "IC5") (pin "9") (pinfunction "Y6_9") (pintype "input"))
      (node (ref "RAM7") (pin "22") (pinfunction "CS_22") (pintype "input"))
    )
    (net (code "30") (name "/CS8") (class "Default")
      (node (ref "IC5") (pin "7") (pinfunction "Y7_7") (pintype "input"))
      (node (ref "RAM8") (pin "22") (pinfunction "CS_22") (pintype "input"))
    )
    (net (code "31") (name "/GND") (class "Default")
      (node (ref "C1") (pin "2") (pinfunction "2_2") (pintype "input"))
      (node (ref "C10") (pin "2") (pinfunction "2_2") (pintype "input"))
      (node (ref "C11") (pin "2") (pinfunction "2_2") (pintype "input"))
      (node (ref "C12") (pin "2") (pinfunction "2_2") (pintype "input"))
      (node (ref "C13") (pin "2") (pinfunction "2_2") (pintype "input"))
      (node (ref "C14") (pin "2") (pinfunction "2_2") (pintype "input"))
      (node (ref "C15") (pin "2") (pinfunction "2_2") (pintype "input"))
      (node (ref "C2") (pin "2") (pinfunction "2_2") (pintype "input"))
      (node (ref "C3") (pin "2") (pinfunction "2_2") (pintype "input"))
      (node (ref "C4") (pin "2") (pinfunction "2_2") (pintype "input"))
      (node (ref "C5") (pin "2") (pinfunction "2_2") (pintype "input"))
      (node (ref "C6") (pin "2") (pinfunction "2_2") (pintype "input"))
      (node (ref "C7") (pin "2") (pinfunction "2_2") (pintype "input"))
      (node (ref "C8") (pin "2") (pinfunction "2_2") (pintype "input"))
      (node (ref "C9") (pin "2") (pinfunction "2_2") (pintype "input"))
      (node (ref "EDGE1") (pin "GND1") (pinfunction "GND_GND1") (pintype "input"))
      (node (ref "EDGE1") (pin "GND2") (pinfunction "GND_GND2") (pintype "input"))
      (node (ref "IC1") (pin "11") (pinfunction "RE#_11") (pintype "input"))
      (node (ref "IC1") (pin "8") (pinfunction "GND_8") (pintype "input"))
      (node (ref "IC2") (pin "11") (pinfunction "RE#_11") (pintype "input"))
      (node (ref "IC2") (pin "8") (pinfunction "GND_8") (pintype "input"))
      (node (ref "IC3") (pin "10") (pinfunction "GND_10") (pintype "input"))
      (node (ref "IC3") (pin "16") (pinfunction "Q6_16") (pintype "input"))
      (node (ref "IC3") (pin "17") (pinfunction "P7_17") (pintype "input"))
      (node (ref "IC3") (pin "18") (pinfunction "Q7_18") (pintype "input"))
      (node (ref "IC4") (pin "8") (pinfunction "GND_8") (pintype "input"))
      (node (ref "IC5") (pin "8") (pinfunction "GND_8") (pintype "input"))
      (node (ref "IC6") (pin "8") (pinfunction "GND_8") (pintype "input"))
      (node (ref "IC7") (pin "7") (pinfunction "GND_7") (pintype "input"))
      (node (ref "RAM1") (pin "16") (pinfunction "VSS_16") (pintype "input"))
      (node (ref "RAM2") (pin "16") (pinfunction "VSS_16") (pintype "input"))
      (node (ref "RAM3") (pin "16") (pinfunction "VSS_16") (pintype "input"))
      (node (ref "RAM4") (pin "16") (pinfunction "VSS_16") (pintype "input"))
      (node (ref "RAM5") (pin "16") (pinfunction "VSS_16") (pintype "input"))
      (node (ref "RAM6") (pin "16") (pinfunction "VSS_16") (pintype "input"))
      (node (ref "RAM7") (pin "16") (pinfunction "VSS_16") (pintype "input"))
      (node (ref "RAM8") (pin "16") (pinfunction "VSS_16") (pintype "input"))
    )
    (net (code "32") (name "/IC2_6") (class "Default")
      (node (ref "IC2") (pin "6") (pinfunction "Q3_6") (pintype "input"))
      (node (ref "IC5") (pin "3") (pinfunction "C_3") (pintype "input"))
    )
    (net (code "33") (name "/IC2_7") (class "Default")
      (node (ref "IC2") (pin "7") (pinfunction "Q2_7") (pintype "input"))
      (node (ref "IC5") (pin "2") (pinfunction "B_2") (pintype "input"))
    )
    (net (code "34") (name "/IC2_9") (class "Default")
      (node (ref "IC2") (pin "9") (pinfunction "Q1_9") (pintype "input"))
      (node (ref "IC5") (pin "1") (pinfunction "A_1") (pintype "input"))
    )
    (net (code "35") (name "/IC7_6") (class "Default")
      (node (ref "IC4") (pin "11") (pinfunction "RE#_11") (pintype "input"))
      (node (ref "IC6") (pin "11") (pinfunction "RE#_11") (pintype "input"))
      (node (ref "IC7") (pin "6") (pinfunction "2Y_6") (pintype "input"))
    )
    (net (code "36") (name "/IO1") (class "Default")
      (node (ref "EDGE1") (pin "IORQ") (pinfunction "!IORQ_IORQ") (pintype "output"))
      (node (ref "IC1") (pin "15") (pinfunction "D0_15") (pintype "input"))
      (node (ref "IC4") (pin "10") (pinfunction "Q0_10") (pintype "input"))
      (node (ref "IC4") (pin "15") (pinfunction "D0_15") (pintype "input"))
      (node (ref "RAM1") (pin "13") (pinfunction "IO1_13") (pintype "input"))
      (node (ref "RAM2") (pin "13") (pinfunction "IO1_13") (pintype "input"))
      (node (ref "RAM3") (pin "13") (pinfunction "IO1_13") (pintype "input"))
      (node (ref "RAM4") (pin "13") (pinfunction "IO1_13") (pintype "input"))
      (node (ref "RAM5") (pin "13") (pinfunction "IO1_13") (pintype "input"))
      (node (ref "RAM6") (pin "13") (pinfunction "IO1_13") (pintype "input"))
      (node (ref "RAM7") (pin "13") (pinfunction "IO1_13") (pintype "input"))
      (node (ref "RAM8") (pin "13") (pinfunction "IO1_13") (pintype "input"))
    )
    (net (code "37") (name "/IO2") (class "Default")
      (node (ref "EDGE1") (pin "SW1") (pinfunction "SW_SW1") (pintype "input"))
      (node (ref "IC1") (pin "1") (pinfunction "D1_1") (pintype "input"))
      (node (ref "IC4") (pin "1") (pinfunction "D1_1") (pintype "input"))
      (node (ref "IC4") (pin "9") (pinfunction "Q1_9") (pintype "input"))
      (node (ref "RAM1") (pin "14") (pinfunction "IO2_14") (pintype "input"))
      (node (ref "RAM2") (pin "14") (pinfunction "IO2_14") (pintype "input"))
      (node (ref "RAM3") (pin "14") (pinfunction "IO2_14") (pintype "input"))
      (node (ref "RAM4") (pin "14") (pinfunction "IO2_14") (pintype "input"))
      (node (ref "RAM5") (pin "14") (pinfunction "IO2_14") (pintype "input"))
      (node (ref "RAM6") (pin "14") (pinfunction "IO2_14") (pintype "input"))
      (node (ref "RAM7") (pin "14") (pinfunction "IO2_14") (pintype "input"))
      (node (ref "RAM8") (pin "14") (pinfunction "IO2_14") (pintype "input"))
    )
    (net (code "38") (name "/IO3") (class "Default")
      (node (ref "EDGE1") (pin "WR") (pinfunction "!WR_WR") (pintype "output"))
      (node (ref "IC1") (pin "2") (pinfunction "D2_2") (pintype "input"))
      (node (ref "IC4") (pin "2") (pinfunction "D2_2") (pintype "input"))
      (node (ref "IC4") (pin "7") (pinfunction "Q2_7") (pintype "input"))
      (node (ref "RAM1") (pin "15") (pinfunction "IO3_15") (pintype "input"))
      (node (ref "RAM2") (pin "15") (pinfunction "IO3_15") (pintype "input"))
      (node (ref "RAM3") (pin "15") (pinfunction "IO3_15") (pintype "input"))
      (node (ref "RAM4") (pin "15") (pinfunction "IO3_15") (pintype "input"))
      (node (ref "RAM5") (pin "15") (pinfunction "IO3_15") (pintype "input"))
      (node (ref "RAM6") (pin "15") (pinfunction "IO3_15") (pintype "input"))
      (node (ref "RAM7") (pin "15") (pinfunction "IO3_15") (pintype "input"))
      (node (ref "RAM8") (pin "15") (pinfunction "IO3_15") (pintype "input"))
    )
    (net (code "39") (name "/IO4") (class "Default")
      (node (ref "EDGE1") (pin "SW2") (pinfunction "SW_SW2") (pintype "input"))
      (node (ref "IC1") (pin "3") (pinfunction "D3_3") (pintype "input"))
      (node (ref "IC4") (pin "3") (pinfunction "D3_3") (pintype "input"))
      (node (ref "IC4") (pin "6") (pinfunction "Q3_6") (pintype "input"))
      (node (ref "RAM1") (pin "17") (pinfunction "IO4_17") (pintype "input"))
      (node (ref "RAM2") (pin "17") (pinfunction "IO4_17") (pintype "input"))
      (node (ref "RAM3") (pin "17") (pinfunction "IO4_17") (pintype "input"))
      (node (ref "RAM4") (pin "17") (pinfunction "IO4_17") (pintype "input"))
      (node (ref "RAM5") (pin "17") (pinfunction "IO4_17") (pintype "input"))
      (node (ref "RAM6") (pin "17") (pinfunction "IO4_17") (pintype "input"))
      (node (ref "RAM7") (pin "17") (pinfunction "IO4_17") (pintype "input"))
      (node (ref "RAM8") (pin "17") (pinfunction "IO4_17") (pintype "input"))
    )
    (net (code "40") (name "/IO5") (class "Default")
      (node (ref "EDGE1") (pin "RD") (pinfunction "!RD_RD") (pintype "output"))
      (node (ref "IC2") (pin "15") (pinfunction "D0_15") (pintype "input"))
      (node (ref "IC6") (pin "10") (pinfunction "Q0_10") (pintype "input"))
      (node (ref "IC6") (pin "15") (pinfunction "D0_15") (pintype "input"))
      (node (ref "RAM1") (pin "18") (pinfunction "IO5_18") (pintype "input"))
      (node (ref "RAM2") (pin "18") (pinfunction "IO5_18") (pintype "input"))
      (node (ref "RAM3") (pin "18") (pinfunction "IO5_18") (pintype "input"))
      (node (ref "RAM4") (pin "18") (pinfunction "IO5_18") (pintype "input"))
      (node (ref "RAM5") (pin "18") (pinfunction "IO5_18") (pintype "input"))
      (node (ref "RAM6") (pin "18") (pinfunction "IO5_18") (pintype "input"))
      (node (ref "RAM7") (pin "18") (pinfunction "IO5_18") (pintype "input"))
      (node (ref "RAM8") (pin "18") (pinfunction "IO5_18") (pintype "input"))
    )
    (net (code "41") (name "/IO6") (class "Default")
      (node (ref "EDGE1") (pin "+12V") (pinfunction "+12V_+12V") (pintype "input"))
      (node (ref "IC2") (pin "1") (pinfunction "D1_1") (pintype "input"))
      (node (ref "IC6") (pin "1") (pinfunction "D1_1") (pintype "input"))
      (node (ref "RAM1") (pin "19") (pinfunction "IO6_19") (pintype "input"))
      (node (ref "RAM2") (pin "19") (pinfunction "IO6_19") (pintype "input"))
      (node (ref "RAM3") (pin "19") (pinfunction "IO6_19") (pintype "input"))
      (node (ref "RAM4") (pin "19") (pinfunction "IO6_19") (pintype "input"))
      (node (ref "RAM5") (pin "19") (pinfunction "IO6_19") (pintype "input"))
      (node (ref "RAM6") (pin "19") (pinfunction "IO6_19") (pintype "input"))
      (node (ref "RAM7") (pin "19") (pinfunction "IO6_19") (pintype "input"))
      (node (ref "RAM8") (pin "19") (pinfunction "IO6_19") (pintype "input"))
    )
    (net (code "42") (name "/IO7") (class "Default")
      (node (ref "EDGE1") (pin "CS1") (pinfunction "!CS1_CS1") (pintype "output"))
      (node (ref "IC2") (pin "2") (pinfunction "D2_2") (pintype "input"))
      (node (ref "IC6") (pin "2") (pinfunction "D2_2") (pintype "input"))
      (node (ref "RAM1") (pin "20") (pinfunction "IO7_20") (pintype "input"))
      (node (ref "RAM2") (pin "20") (pinfunction "IO7_20") (pintype "input"))
      (node (ref "RAM3") (pin "20") (pinfunction "IO7_20") (pintype "input"))
      (node (ref "RAM4") (pin "20") (pinfunction "IO7_20") (pintype "input"))
      (node (ref "RAM5") (pin "20") (pinfunction "IO7_20") (pintype "input"))
      (node (ref "RAM6") (pin "20") (pinfunction "IO7_20") (pintype "input"))
      (node (ref "RAM7") (pin "20") (pinfunction "IO7_20") (pintype "input"))
      (node (ref "RAM8") (pin "20") (pinfunction "IO7_20") (pintype "input"))
    )
    (net (code "43") (name "/IO8") (class "Default")
      (node (ref "EDGE1") (pin "-12V") (pinfunction "-12V_-12V") (pintype "input"))
      (node (ref "IC2") (pin "3") (pinfunction "D3_3") (pintype "input"))
      (node (ref "IC6") (pin "3") (pinfunction "D3_3") (pintype "input"))
      (node (ref "RAM1") (pin "21") (pinfunction "IO8_21") (pintype "input"))
      (node (ref "RAM2") (pin "21") (pinfunction "IO8_21") (pintype "input"))
      (node (ref "RAM3") (pin "21") (pinfunction "IO8_21") (pintype "input"))
      (node (ref "RAM4") (pin "21") (pinfunction "IO8_21") (pintype "input"))
      (node (ref "RAM5") (pin "21") (pinfunction "IO8_21") (pintype "input"))
      (node (ref "RAM6") (pin "21") (pinfunction "IO8_21") (pintype "input"))
      (node (ref "RAM7") (pin "21") (pinfunction "IO8_21") (pintype "input"))
      (node (ref "RAM8") (pin "21") (pinfunction "IO8_21") (pintype "input"))
    )
    (net (code "44") (name "/OE") (class "Default")
      (node (ref "EDGE1") (pin "D6") (pinfunction "D6_D6") (pintype "input"))
      (node (ref "IC7") (pin "4") (pinfunction "2A_4") (pintype "input"))
      (node (ref "RAM1") (pin "24") (pinfunction "OE_24") (pintype "input"))
      (node (ref "RAM2") (pin "24") (pinfunction "OE_24") (pintype "input"))
      (node (ref "RAM3") (pin "24") (pinfunction "OE_24") (pintype "input"))
      (node (ref "RAM4") (pin "24") (pinfunction "OE_24") (pintype "input"))
      (node (ref "RAM5") (pin "24") (pinfunction "OE_24") (pintype "input"))
      (node (ref "RAM6") (pin "24") (pinfunction "OE_24") (pintype "input"))
      (node (ref "RAM7") (pin "24") (pinfunction "OE_24") (pintype "input"))
      (node (ref "RAM8") (pin "24") (pinfunction "OE_24") (pintype "input"))
    )
    (net (code "45") (name "/R1_1") (class "Default")
      (node (ref "IC1") (pin "12") (pinfunction "WE#_12") (pintype "input"))
      (node (ref "IC2") (pin "12") (pinfunction "WE#_12") (pintype "input"))
      (node (ref "IC4") (pin "12") (pinfunction "WE#_12") (pintype "input"))
      (node (ref "IC6") (pin "12") (pinfunction "WE#_12") (pintype "input"))
      (node (ref "IC7") (pin "3") (pinfunction "1Y_3") (pintype "input"))
      (node (ref "R1") (pin "1") (pinfunction "1_1") (pintype "input"))
    )
    (net (code "46") (name "/R1_2") (class "Default")
      (node (ref "IC3") (pin "19") (pinfunction "P=Q#_19") (pintype "input"))
      (node (ref "IC7") (pin "2") (pinfunction "1B_2") (pintype "input"))
      (node (ref "IC7") (pin "5") (pinfunction "2B_5") (pintype "input"))
      (node (ref "R1") (pin "2") (pinfunction "2_2") (pintype "input"))
    )
    (net (code "47") (name "/T17") (class "Default")
      (node (ref "EDGE1") (pin "BUSDIR") (pinfunction "!BUSDIR_BUSDIR") (pintype "input"))
      (node (ref "IC1") (pin "4") (pinfunction "RA1_4") (pintype "input"))
      (node (ref "IC2") (pin "4") (pinfunction "RA1_4") (pintype "input"))
    )
    (net (code "48") (name "/T24") (class "Default")
      (node (ref "EDGE1") (pin "D1") (pinfunction "D1_D1") (pintype "input"))
      (node (ref "IC5") (pin "4") (pinfunction "G#/2A_4") (pintype "input"))
      (node (ref "IC5") (pin "5") (pinfunction "G#/2B_5") (pintype "input"))
    )
    (net (code "49") (name "/WE") (class "Default")
      (node (ref "EDGE1") (pin "A6") (pinfunction "A6_A6") (pintype "output"))
      (node (ref "IC3") (pin "15") (pinfunction "P6_15") (pintype "input"))
      (node (ref "IC7") (pin "1") (pinfunction "1A_1") (pintype "input"))
      (node (ref "RAM1") (pin "29") (pinfunction "WE_29") (pintype "input"))
      (node (ref "RAM2") (pin "29") (pinfunction "WE_29") (pintype "input"))
      (node (ref "RAM3") (pin "29") (pinfunction "WE_29") (pintype "input"))
      (node (ref "RAM4") (pin "29") (pinfunction "WE_29") (pintype "input"))
      (node (ref "RAM5") (pin "29") (pinfunction "WE_29") (pintype "input"))
      (node (ref "RAM6") (pin "29") (pinfunction "WE_29") (pintype "input"))
      (node (ref "RAM7") (pin "29") (pinfunction "WE_29") (pintype "input"))
      (node (ref "RAM8") (pin "29") (pinfunction "WE_29") (pintype "input"))
    )
    (net (code "50") (name "Net-(EDGE1-!CS12)") (class "Default")
      (node (ref "EDGE1") (pin "CS12") (pinfunction "!CS12_CS12") (pintype "output"))
      (node (ref "EDGE1") (pin "SLTSL") (pinfunction "!SLTSL_SLTSL") (pintype "output"))
    )
    (net (code "51") (name "unconnected-(EDGE1-!CS2-PadCS2)") (class "Default")
      (node (ref "EDGE1") (pin "CS2") (pinfunction "!CS2_CS2") (pintype "output+no_connect"))
    )
    (net (code "52") (name "unconnected-(EDGE1-PadA0)") (class "Default")
      (node (ref "EDGE1") (pin "A0") (pinfunction "A0_A0") (pintype "output+no_connect"))
    )
    (net (code "53") (name "unconnected-(EDGE1-PadA1)") (class "Default")
      (node (ref "EDGE1") (pin "A1") (pinfunction "A1_A1") (pintype "output+no_connect"))
    )
    (net (code "54") (name "unconnected-(EDGE1-PadA2)") (class "Default")
      (node (ref "EDGE1") (pin "A2") (pinfunction "A2_A2") (pintype "output+no_connect"))
    )
    (net (code "55") (name "unconnected-(EDGE1-PadA3)") (class "Default")
      (node (ref "EDGE1") (pin "A3") (pinfunction "A3_A3") (pintype "output+no_connect"))
    )
    (net (code "56") (name "unconnected-(EDGE1-PadA4)") (class "Default")
      (node (ref "EDGE1") (pin "A4") (pinfunction "A4_A4") (pintype "output+no_connect"))
    )
    (net (code "57") (name "unconnected-(EDGE1-PadA7)") (class "Default")
      (node (ref "EDGE1") (pin "A7") (pinfunction "A7_A7") (pintype "output+no_connect"))
    )
    (net (code "58") (name "unconnected-(EDGE1-PadD0)") (class "Default")
      (node (ref "EDGE1") (pin "D0") (pinfunction "D0_D0") (pintype "input+no_connect"))
    )
    (net (code "59") (name "unconnected-(EDGE1-PadD2)") (class "Default")
      (node (ref "EDGE1") (pin "D2") (pinfunction "D2_D2") (pintype "input+no_connect"))
    )
    (net (code "60") (name "unconnected-(EDGE1-PadD3)") (class "Default")
      (node (ref "EDGE1") (pin "D3") (pinfunction "D3_D3") (pintype "input+no_connect"))
    )
    (net (code "61") (name "unconnected-(EDGE1-PadD4)") (class "Default")
      (node (ref "EDGE1") (pin "D4") (pinfunction "D4_D4") (pintype "input+no_connect"))
    )
    (net (code "62") (name "unconnected-(EDGE1-PadD5)") (class "Default")
      (node (ref "EDGE1") (pin "D5") (pinfunction "D5_D5") (pintype "input+no_connect"))
    )
    (net (code "63") (name "unconnected-(EDGE1-PadD7)") (class "Default")
      (node (ref "EDGE1") (pin "D7") (pinfunction "D7_D7") (pintype "input+no_connect"))
    )
    (net (code "64") (name "unconnected-(EDGE1-PadSOUNDIN)") (class "Default")
      (node (ref "EDGE1") (pin "SOUNDIN") (pinfunction "SOUNDIN_SOUNDIN") (pintype "input+no_connect"))
    )
    (net (code "65") (name "unconnected-(EDGE1-RES-PadRESV1)") (class "Default")
      (node (ref "EDGE1") (pin "RESV1") (pinfunction "RES_RESV1") (pintype "input+no_connect"))
    )
    (net (code "66") (name "unconnected-(EDGE1-RES-PadRESV2)") (class "Default")
      (node (ref "EDGE1") (pin "RESV2") (pinfunction "RES_RESV2") (pintype "input+no_connect"))
    )
    (net (code "67") (name "unconnected-(IC6-Q1-Pad9)") (class "Default")
      (node (ref "IC6") (pin "9") (pinfunction "Q1_9") (pintype "input+no_connect"))
    )
    (net (code "68") (name "unconnected-(IC6-Q2-Pad7)") (class "Default")
      (node (ref "IC6") (pin "7") (pinfunction "Q2_7") (pintype "input+no_connect"))
    )
    (net (code "69") (name "unconnected-(IC6-Q3-Pad6)") (class "Default")
      (node (ref "IC6") (pin "6") (pinfunction "Q3_6") (pintype "input+no_connect"))
    )
    (net (code "70") (name "unconnected-(IC7-3A-Pad9)") (class "Default")
      (node (ref "IC7") (pin "9") (pinfunction "3A_9") (pintype "input+no_connect"))
    )
    (net (code "71") (name "unconnected-(IC7-3B-Pad10)") (class "Default")
      (node (ref "IC7") (pin "10") (pinfunction "3B_10") (pintype "input+no_connect"))
    )
    (net (code "72") (name "unconnected-(IC7-3Y-Pad8)") (class "Default")
      (node (ref "IC7") (pin "8") (pinfunction "3Y_8") (pintype "input+no_connect"))
    )
    (net (code "73") (name "unconnected-(IC7-4A-Pad12)") (class "Default")
      (node (ref "IC7") (pin "12") (pinfunction "4A_12") (pintype "input+no_connect"))
    )
    (net (code "74") (name "unconnected-(IC7-4B-Pad13)") (class "Default")
      (node (ref "IC7") (pin "13") (pinfunction "4B_13") (pintype "input+no_connect"))
    )
    (net (code "75") (name "unconnected-(IC7-4Y-Pad11)") (class "Default")
      (node (ref "IC7") (pin "11") (pinfunction "4Y_11") (pintype "input+no_connect"))
    )
  )
)
